# 388_Design_Project_Schematic.net
KiCad netlist of a schematic drawn in EAGLE
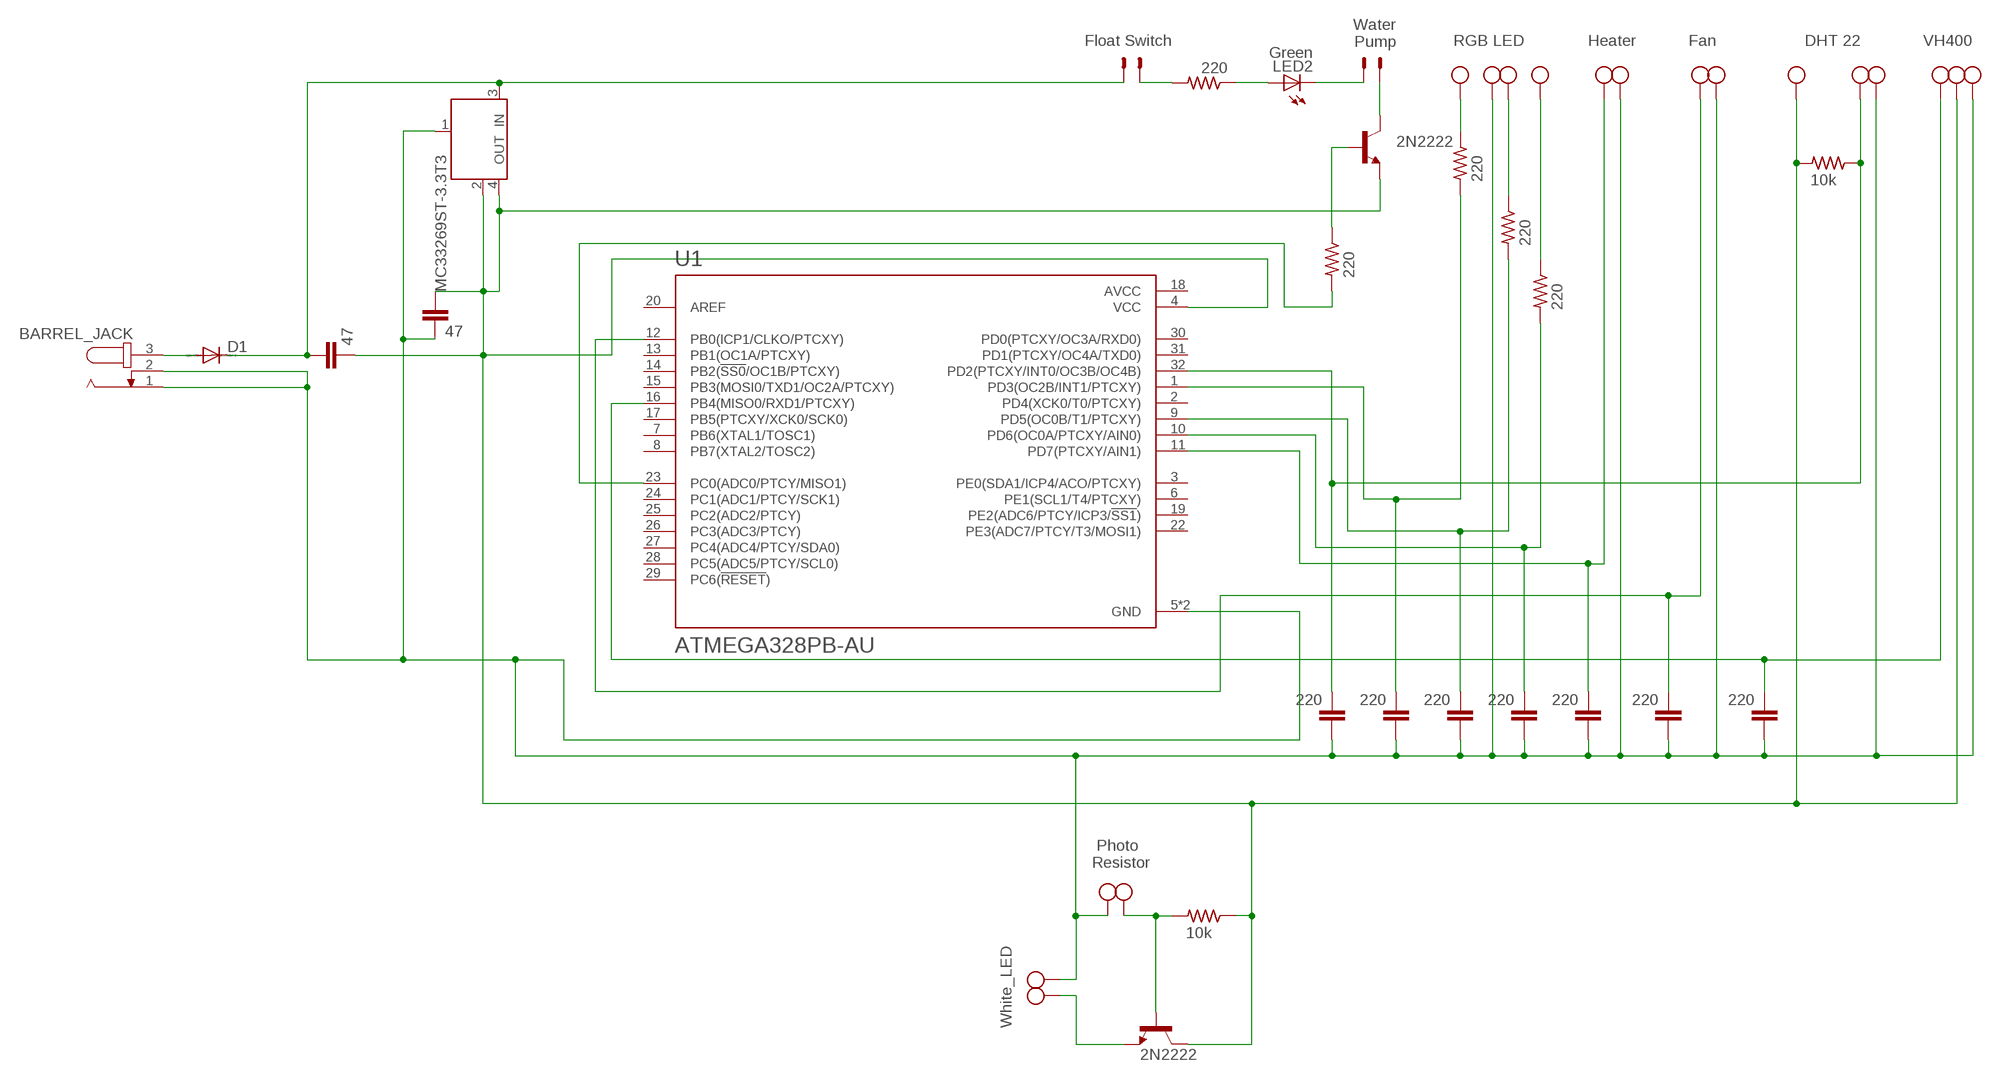
[diagram p0: schematic, sheet 1]

(export (version "E")
  (design (tool "Eeschema 10.0.6"))
  (components
    (comp (ref "BARREL_JACK")
      (value "JACK-PLUG1")
      (footprint "eagle-import:SPC4078")
      (libsource (lib "eagle-import") (part "JACK-PLUG1"))
    )
    (comp (ref "C2")
      (value "220")
      (footprint "eagle-import:C025-024X044")
      (libsource (lib "eagle-import") (part "C-EU025-024X044"))
    )
    (comp (ref "C4")
      (value "220")
      (footprint "eagle-import:C025-024X044")
      (libsource (lib "eagle-import") (part "C-EU025-024X044"))
    )
    (comp (ref "C5")
      (value "220")
      (footprint "eagle-import:C025-024X044")
      (libsource (lib "eagle-import") (part "C-EU025-024X044"))
    )
    (comp (ref "C6")
      (value "220")
      (footprint "eagle-import:C025-024X044")
      (libsource (lib "eagle-import") (part "C-EU025-024X044"))
    )
    (comp (ref "C7")
      (value "220")
      (footprint "eagle-import:C025-024X044")
      (libsource (lib "eagle-import") (part "C-EU025-024X044"))
    )
    (comp (ref "C8")
      (value "47")
      (footprint "eagle-import:C025-024X044")
      (libsource (lib "eagle-import") (part "C-EU025-024X044"))
    )
    (comp (ref "C9")
      (value "47")
      (footprint "eagle-import:C025-024X044")
      (libsource (lib "eagle-import") (part "C-EU025-024X044"))
    )
    (comp (ref "C10")
      (value "220")
      (footprint "eagle-import:C025-024X044")
      (libsource (lib "eagle-import") (part "C-EU025-024X044"))
    )
    (comp (ref "C11")
      (value "220")
      (footprint "eagle-import:C025-024X044")
      (libsource (lib "eagle-import") (part "C-EU025-024X044"))
    )
    (comp (ref "D1")
      (value "DIODE-DO214BA")
      (footprint "eagle-import:DO214BA")
      (libsource (lib "eagle-import") (part "DIODE-DO214BA"))
    )
    (comp (ref "IC1")
      (value "MC33269ST-3.3T3")
      (footprint "eagle-import:SOT223")
      (libsource (lib "eagle-import") (part "MC33269ST-3.3T3"))
    )
    (comp (ref "LED2")
      (value "Green")
      (footprint "eagle-import:CHIPLED_0805")
      (libsource (lib "eagle-import") (part "LEDCHIPLED_0805"))
    )
    (comp (ref "R1")
      (value "220")
      (footprint "eagle-import:R0805")
      (libsource (lib "eagle-import") (part "R-US_R0805"))
    )
    (comp (ref "R2")
      (value "220")
      (footprint "eagle-import:R0805")
      (libsource (lib "eagle-import") (part "R-US_R0805"))
    )
    (comp (ref "R3")
      (value "10k")
      (footprint "eagle-import:R0805")
      (libsource (lib "eagle-import") (part "R-US_R0805"))
    )
    (comp (ref "R4")
      (value "220")
      (footprint "eagle-import:R0805")
      (libsource (lib "eagle-import") (part "R-US_R0805"))
    )
    (comp (ref "R6")
      (value "220")
      (footprint "eagle-import:R0805")
      (libsource (lib "eagle-import") (part "R-US_R0805"))
    )
    (comp (ref "R7")
      (value "220")
      (footprint "eagle-import:R0805")
      (libsource (lib "eagle-import") (part "R-US_R0805"))
    )
    (comp (ref "R8")
      (value "10k")
      (footprint "eagle-import:R0805")
      (libsource (lib "eagle-import") (part "R-US_R0805"))
    )
    (comp (ref "T1")
      (value "2N2222")
      (footprint "eagle-import:TO18")
      (libsource (lib "eagle-import") (part "2N2222"))
    )
    (comp (ref "T2")
      (value "2N2222")
      (footprint "eagle-import:TO18")
      (libsource (lib "eagle-import") (part "2N2222"))
    )
    (comp (ref "U1")
      (value "ATMEGA328PB-AU")
      (footprint "eagle-import:QFP80P900X900X120-32N")
      (fields (field (name "MF") "Microchip"))
      (libsource (lib "eagle-import") (part "ATMEGA328PB-AU"))
    )
    (comp (ref "WHITE_LED")
      (value "AK300/2")
      (footprint "eagle-import:AK300_2")
      (libsource (lib "eagle-import") (part "AK300/2"))
    )
    (comp (ref "X1")
      (value "1X02_5MM_SCREW")
      (footprint "eagle-import:W237-102")
      (fields (field (name "MPN") "237-102"))
      (libsource (lib "eagle-import") (part "1X02_5MM_SCREW"))
    )
    (comp (ref "X2")
      (value "AK300/2")
      (footprint "eagle-import:AK300_2")
      (libsource (lib "eagle-import") (part "AK300/2"))
    )
    (comp (ref "X4")
      (value "1X02_5MM_SCREW")
      (footprint "eagle-import:W237-102")
      (fields (field (name "MPN") "237-102"))
      (libsource (lib "eagle-import") (part "1X02_5MM_SCREW"))
    )
    (comp (ref "X5")
      (value "AK300/3")
      (footprint "eagle-import:AK300_3")
      (libsource (lib "eagle-import") (part "AK300/3"))
    )
    (comp (ref "X6")
      (value "AK300/4")
      (footprint "eagle-import:AK300_4")
      (libsource (lib "eagle-import") (part "AK300/4"))
    )
    (comp (ref "X7")
      (value "AK300/3")
      (footprint "eagle-import:AK300_3")
      (libsource (lib "eagle-import") (part "AK300/3"))
    )
    (comp (ref "X8")
      (value "1X02_5MM_SCREW")
      (footprint "eagle-import:W237-102")
      (fields (field (name "MPN") "237-102"))
      (libsource (lib "eagle-import") (part "1X02_5MM_SCREW"))
    )
    (comp (ref "X9")
      (value "332-02")
      (footprint "eagle-import:332-02")
      (libsource (lib "eagle-import") (part "332-02"))
    )
    (comp (ref "X10")
      (value "332-02")
      (footprint "eagle-import:332-02")
      (libsource (lib "eagle-import") (part "332-02"))
    )
  )
  (nets
    (net (code "1") (name "/AVCC") (class "Default")
      (node (ref "U1") (pin "18") (pinfunction "AVCC_18") (pintype "power_in"))
    )
    (net (code "2") (name "Net-(BARREL_JACK-Pad3)") (class "Default")
      (node (ref "BARREL_JACK") (pin "3") (pinfunction "3_3") (pintype "passive"))
      (node (ref "D1") (pin "A") (pinfunction "A_A") (pintype "passive"))
    )
    (net (code "3") (name "Net-(IC1-GND{slash}ADJ)") (class "Default")
      (node (ref "BARREL_JACK") (pin "1") (pinfunction "1_1") (pintype "passive"))
      (node (ref "BARREL_JACK") (pin "2") (pinfunction "2_2") (pintype "passive"))
      (node (ref "C10") (pin "1") (pinfunction "1_1") (pintype "passive"))
      (node (ref "C11") (pin "1") (pinfunction "1_1") (pintype "passive"))
      (node (ref "C2") (pin "1") (pinfunction "1_1") (pintype "passive"))
      (node (ref "C4") (pin "1") (pinfunction "1_1") (pintype "passive"))
      (node (ref "C5") (pin "1") (pinfunction "1_1") (pintype "passive"))
      (node (ref "C6") (pin "1") (pinfunction "1_1") (pintype "passive"))
      (node (ref "C7") (pin "1") (pinfunction "1_1") (pintype "passive"))
      (node (ref "C9") (pin "2") (pinfunction "2_2") (pintype "passive"))
      (node (ref "IC1") (pin "1") (pinfunction "GND/ADJ_1") (pintype "input"))
      (node (ref "U1") (pin "21") (pinfunction "GND_21") (pintype "power_in"))
      (node (ref "U1") (pin "5") (pinfunction "GND_5") (pintype "power_in"))
      (node (ref "WHITE_LED") (pin "2") (pinfunction "KL_2") (pintype "passive"))
      (node (ref "X1") (pin "2") (pinfunction "KL_2") (pintype "passive"))
      (node (ref "X2") (pin "1") (pinfunction "KL_1") (pintype "passive"))
      (node (ref "X4") (pin "1") (pinfunction "KL_1") (pintype "passive"))
      (node (ref "X6") (pin "3") (pinfunction "KL_3") (pintype "passive"))
      (node (ref "X7") (pin "1") (pinfunction "KL_1") (pintype "passive"))
      (node (ref "X8") (pin "1") (pinfunction "KL_1") (pintype "passive"))
    )
    (net (code "4") (name "Net-(IC1-IN)") (class "Default")
      (node (ref "C8") (pin "1") (pinfunction "1_1") (pintype "passive"))
      (node (ref "D1") (pin "C") (pinfunction "C_C") (pintype "passive"))
      (node (ref "IC1") (pin "3") (pinfunction "IN_3") (pintype "input"))
      (node (ref "X10") (pin "2") (pinfunction "S_2") (pintype "passive"))
    )
    (net (code "5") (name "Net-(LED2-PadA)") (class "Default")
      (node (ref "LED2") (pin "A") (pinfunction "A_A") (pintype "passive"))
      (node (ref "R1") (pin "1") (pinfunction "1_1") (pintype "passive"))
    )
    (net (code "6") (name "Net-(T1-B)") (class "Default")
      (node (ref "R4") (pin "1") (pinfunction "1_1") (pintype "passive"))
      (node (ref "T1") (pin "2") (pinfunction "B_2") (pintype "passive"))
    )
    (net (code "7") (name "Net-(T1-C)") (class "Default")
      (node (ref "T1") (pin "3") (pinfunction "C_3") (pintype "passive"))
      (node (ref "X9") (pin "2") (pinfunction "S_2") (pintype "passive"))
    )
    (net (code "8") (name "Net-(T1-E)") (class "Default")
      (node (ref "C8") (pin "2") (pinfunction "2_2") (pintype "passive"))
      (node (ref "C9") (pin "1") (pinfunction "1_1") (pintype "passive"))
      (node (ref "IC1") (pin "2") (pinfunction "OUT_2") (pintype "passive"))
      (node (ref "IC1") (pin "4") (pinfunction "OUT_4") (pintype "passive"))
      (node (ref "R3") (pin "1") (pinfunction "1_1") (pintype "passive"))
      (node (ref "R8") (pin "2") (pinfunction "2_2") (pintype "passive"))
      (node (ref "T1") (pin "1") (pinfunction "E_1") (pintype "passive"))
      (node (ref "T2") (pin "3") (pinfunction "C_3") (pintype "passive"))
      (node (ref "U1") (pin "4") (pinfunction "VCC_4") (pintype "power_in"))
      (node (ref "X5") (pin "3") (pinfunction "KL_3") (pintype "passive"))
      (node (ref "X7") (pin "2") (pinfunction "KL_2") (pintype "passive"))
    )
    (net (code "9") (name "Net-(T2-B)") (class "Default")
      (node (ref "R3") (pin "2") (pinfunction "2_2") (pintype "passive"))
      (node (ref "T2") (pin "2") (pinfunction "B_2") (pintype "passive"))
      (node (ref "X2") (pin "2") (pinfunction "KL_2") (pintype "passive"))
    )
    (net (code "10") (name "Net-(T2-E)") (class "Default")
      (node (ref "T2") (pin "1") (pinfunction "E_1") (pintype "passive"))
      (node (ref "WHITE_LED") (pin "1") (pinfunction "KL_1") (pintype "passive"))
    )
    (net (code "11") (name "Net-(U1-PB0(ICP1{slash}CLKO{slash}PTCXY))") (class "Default")
      (node (ref "C10") (pin "2") (pinfunction "2_2") (pintype "passive"))
      (node (ref "U1") (pin "12") (pinfunction "PB0(ICP1/CLKO/PTCXY)_12") (pintype "bidirectional"))
      (node (ref "X8") (pin "2") (pinfunction "KL_2") (pintype "passive"))
    )
    (net (code "12") (name "Net-(U1-PB4(MISO0{slash}RXD1{slash}PTCXY))") (class "Default")
      (node (ref "C11") (pin "2") (pinfunction "2_2") (pintype "passive"))
      (node (ref "U1") (pin "16") (pinfunction "PB4(MISO0/RXD1/PTCXY)_16") (pintype "bidirectional"))
      (node (ref "X7") (pin "3") (pinfunction "KL_3") (pintype "passive"))
    )
    (net (code "13") (name "Net-(U1-PC0(ADC0{slash}PTCY{slash}MISO1))") (class "Default")
      (node (ref "R4") (pin "2") (pinfunction "2_2") (pintype "passive"))
      (node (ref "U1") (pin "23") (pinfunction "PC0(ADC0/PTCY/MISO1)_23") (pintype "bidirectional"))
    )
    (net (code "14") (name "Net-(U1-PD2(PTCXY{slash}INT0{slash}OC3B{slash}OC4B))") (class "Default")
      (node (ref "C6") (pin "2") (pinfunction "2_2") (pintype "passive"))
      (node (ref "R8") (pin "1") (pinfunction "1_1") (pintype "passive"))
      (node (ref "U1") (pin "32") (pinfunction "PD2(PTCXY/INT0/OC3B/OC4B)_32") (pintype "bidirectional"))
      (node (ref "X1") (pin "1") (pinfunction "KL_1") (pintype "passive"))
    )
    (net (code "15") (name "Net-(U1-PD3(OC2B{slash}INT1{slash}PTCXY))") (class "Default")
      (node (ref "C7") (pin "2") (pinfunction "2_2") (pintype "passive"))
      (node (ref "R2") (pin "2") (pinfunction "2_2") (pintype "passive"))
      (node (ref "U1") (pin "1") (pinfunction "PD3(OC2B/INT1/PTCXY)_1") (pintype "bidirectional"))
    )
    (net (code "16") (name "Net-(U1-PD5(OC0B{slash}T1{slash}PTCXY))") (class "Default")
      (node (ref "C4") (pin "2") (pinfunction "2_2") (pintype "passive"))
      (node (ref "R6") (pin "2") (pinfunction "2_2") (pintype "passive"))
      (node (ref "U1") (pin "9") (pinfunction "PD5(OC0B/T1/PTCXY)_9") (pintype "bidirectional"))
    )
    (net (code "17") (name "Net-(U1-PD6(OC0A{slash}PTCXY{slash}AIN0))") (class "Default")
      (node (ref "C5") (pin "2") (pinfunction "2_2") (pintype "passive"))
      (node (ref "R7") (pin "2") (pinfunction "2_2") (pintype "passive"))
      (node (ref "U1") (pin "10") (pinfunction "PD6(OC0A/PTCXY/AIN0)_10") (pintype "bidirectional"))
    )
    (net (code "18") (name "Net-(U1-PD7(PTCXY{slash}AIN1))") (class "Default")
      (node (ref "C2") (pin "2") (pinfunction "2_2") (pintype "passive"))
      (node (ref "U1") (pin "11") (pinfunction "PD7(PTCXY/AIN1)_11") (pintype "bidirectional"))
      (node (ref "X4") (pin "2") (pinfunction "KL_2") (pintype "passive"))
    )
    (net (code "19") (name "Net-(X6A-KL)") (class "Default")
      (node (ref "R7") (pin "1") (pinfunction "1_1") (pintype "passive"))
      (node (ref "X6") (pin "1") (pinfunction "KL_1") (pintype "passive"))
    )
    (net (code "20") (name "Net-(X6B-KL)") (class "Default")
      (node (ref "R6") (pin "1") (pinfunction "1_1") (pintype "passive"))
      (node (ref "X6") (pin "2") (pinfunction "KL_2") (pintype "passive"))
    )
    (net (code "21") (name "Net-(X6D-KL)") (class "Default")
      (node (ref "R2") (pin "1") (pinfunction "1_1") (pintype "passive"))
      (node (ref "X6") (pin "4") (pinfunction "KL_4") (pintype "passive"))
    )
    (net (code "22") (name "Net-(X9A-S)") (class "Default")
      (node (ref "LED2") (pin "C") (pinfunction "C_C") (pintype "passive"))
      (node (ref "X9") (pin "1") (pinfunction "S_1") (pintype "passive"))
    )
    (net (code "23") (name "Net-(X10A-S)") (class "Default")
      (node (ref "R1") (pin "2") (pinfunction "2_2") (pintype "passive"))
      (node (ref "X10") (pin "1") (pinfunction "S_1") (pintype "passive"))
    )
    (net (code "24") (name "unconnected-(U1-AREF-Pad20)") (class "Default")
      (node (ref "U1") (pin "20") (pinfunction "AREF_20") (pintype "input"))
    )
    (net (code "25") (name "unconnected-(U1-PB1(OC1A{slash}PTCXY)-Pad13)") (class "Default")
      (node (ref "U1") (pin "13") (pinfunction "PB1(OC1A/PTCXY)_13") (pintype "bidirectional"))
    )
    (net (code "26") (name "unconnected-(U1-PB2(~{SS0}{slash}OC1B{slash}PTCXY)-Pad14)") (class "Default")
      (node (ref "U1") (pin "14") (pinfunction "PB2(~{SS0}/OC1B/PTCXY)_14") (pintype "bidirectional"))
    )
    (net (code "27") (name "unconnected-(U1-PB3(MOSI0{slash}TXD1{slash}OC2A{slash}PTCXY)-Pad15)") (class "Default")
      (node (ref "U1") (pin "15") (pinfunction "PB3(MOSI0/TXD1/OC2A/PTCXY)_15") (pintype "bidirectional"))
    )
    (net (code "28") (name "unconnected-(U1-PB5(PTCXY{slash}XCK0{slash}SCK0)-Pad17)") (class "Default")
      (node (ref "U1") (pin "17") (pinfunction "PB5(PTCXY/XCK0/SCK0)_17") (pintype "bidirectional"))
    )
    (net (code "29") (name "unconnected-(U1-PB6(XTAL1{slash}TOSC1)-Pad7)") (class "Default")
      (node (ref "U1") (pin "7") (pinfunction "PB6(XTAL1/TOSC1)_7") (pintype "bidirectional"))
    )
    (net (code "30") (name "unconnected-(U1-PB7(XTAL2{slash}TOSC2)-Pad8)") (class "Default")
      (node (ref "U1") (pin "8") (pinfunction "PB7(XTAL2/TOSC2)_8") (pintype "bidirectional"))
    )
    (net (code "31") (name "unconnected-(U1-PC1(ADC1{slash}PTCY{slash}SCK1)-Pad24)") (class "Default")
      (node (ref "U1") (pin "24") (pinfunction "PC1(ADC1/PTCY/SCK1)_24") (pintype "bidirectional"))
    )
    (net (code "32") (name "unconnected-(U1-PC2(ADC2{slash}PTCY)-Pad25)") (class "Default")
      (node (ref "U1") (pin "25") (pinfunction "PC2(ADC2/PTCY)_25") (pintype "bidirectional"))
    )
    (net (code "33") (name "unconnected-(U1-PC3(ADC3{slash}PTCY)-Pad26)") (class "Default")
      (node (ref "U1") (pin "26") (pinfunction "PC3(ADC3/PTCY)_26") (pintype "bidirectional"))
    )
    (net (code "34") (name "unconnected-(U1-PC4(ADC4{slash}PTCY{slash}SDA0)-Pad27)") (class "Default")
      (node (ref "U1") (pin "27") (pinfunction "PC4(ADC4/PTCY/SDA0)_27") (pintype "bidirectional"))
    )
    (net (code "35") (name "unconnected-(U1-PC5(ADC5{slash}PTCY{slash}SCL0)-Pad28)") (class "Default")
      (node (ref "U1") (pin "28") (pinfunction "PC5(ADC5/PTCY/SCL0)_28") (pintype "bidirectional"))
    )
    (net (code "36") (name "unconnected-(U1-PC6(~{RESET})-Pad29)") (class "Default")
      (node (ref "U1") (pin "29") (pinfunction "PC6(~{RESET})_29") (pintype "bidirectional"))
    )
    (net (code "37") (name "unconnected-(U1-PD0(PTCXY{slash}OC3A{slash}RXD0)-Pad30)") (class "Default")
      (node (ref "U1") (pin "30") (pinfunction "PD0(PTCXY/OC3A/RXD0)_30") (pintype "bidirectional"))
    )
    (net (code "38") (name "unconnected-(U1-PD1(PTCXY{slash}OC4A{slash}TXD0)-Pad31)") (class "Default")
      (node (ref "U1") (pin "31") (pinfunction "PD1(PTCXY/OC4A/TXD0)_31") (pintype "bidirectional"))
    )
    (net (code "39") (name "unconnected-(U1-PD4(XCK0{slash}T0{slash}PTCXY)-Pad2)") (class "Default")
      (node (ref "U1") (pin "2") (pinfunction "PD4(XCK0/T0/PTCXY)_2") (pintype "bidirectional"))
    )
    (net (code "40") (name "unconnected-(U1-PE0(SDA1{slash}ICP4{slash}ACO{slash}PTCXY)-Pad3)") (class "Default")
      (node (ref "U1") (pin "3") (pinfunction "PE0(SDA1/ICP4/ACO/PTCXY)_3") (pintype "bidirectional"))
    )
    (net (code "41") (name "unconnected-(U1-PE1(SCL1{slash}T4{slash}PTCXY)-Pad6)") (class "Default")
      (node (ref "U1") (pin "6") (pinfunction "PE1(SCL1/T4/PTCXY)_6") (pintype "bidirectional"))
    )
    (net (code "42") (name "unconnected-(U1-PE2(ADC6{slash}PTCY{slash}ICP3{slash}~{SS1})-Pad19)") (class "Default")
      (node (ref "U1") (pin "19") (pinfunction "PE2(ADC6/PTCY/ICP3/~{SS1})_19") (pintype "bidirectional"))
    )
    (net (code "43") (name "unconnected-(U1-PE3(ADC7{slash}PTCY{slash}T3{slash}MOSI1)-Pad22)") (class "Default")
      (node (ref "U1") (pin "22") (pinfunction "PE3(ADC7/PTCY/T3/MOSI1)_22") (pintype "bidirectional"))
    )
  )
)
